# pads.net
KiCad netlist of a schematic drawn in EAGLE
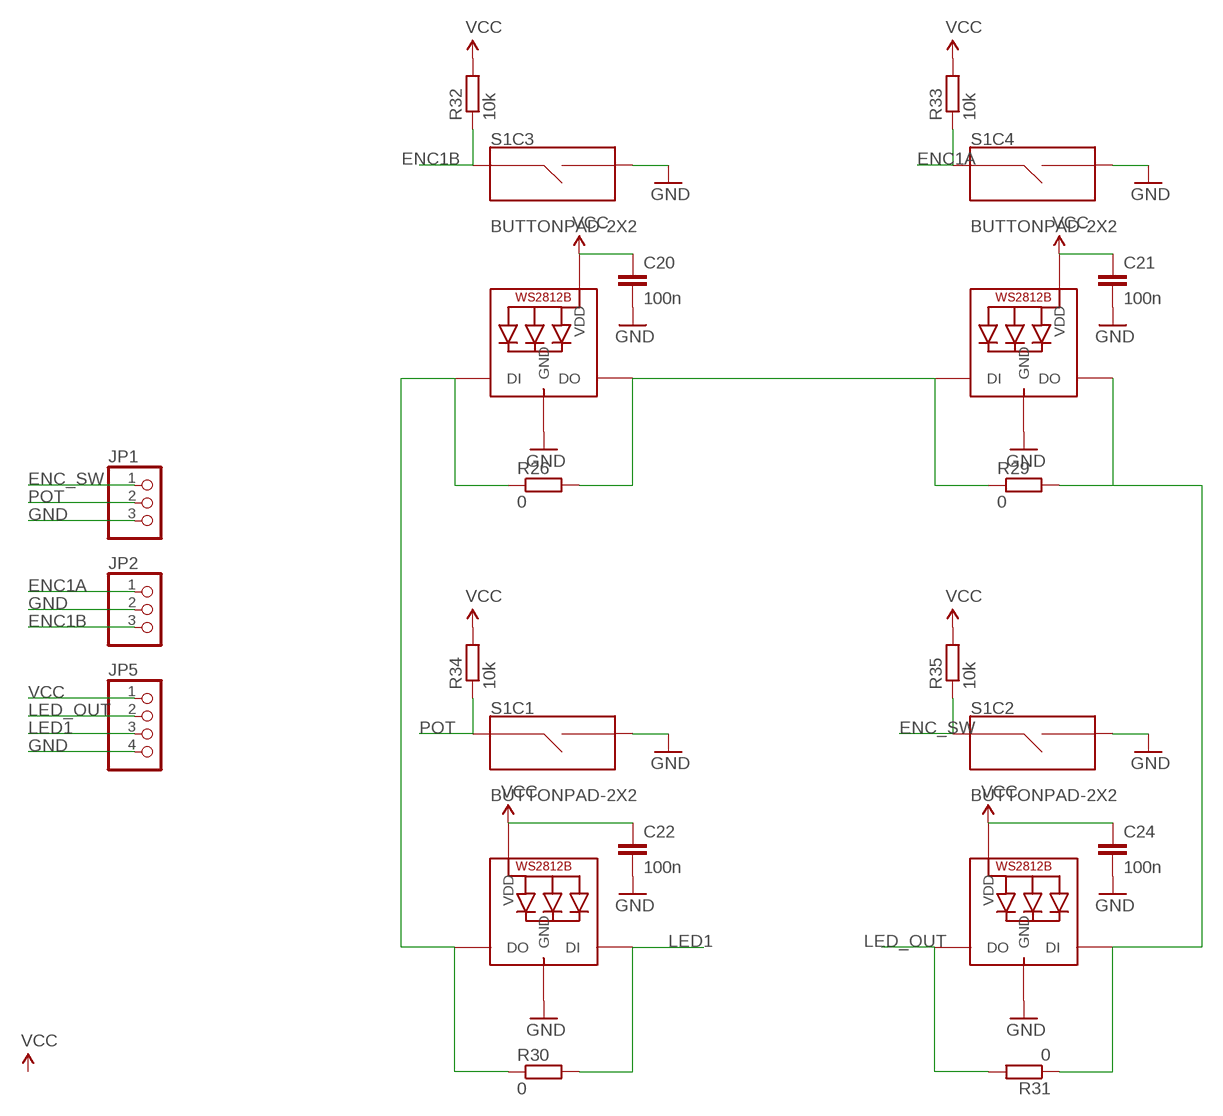
[diagram p0: schematic, sheet 1]

(export (version "E")
  (design (tool "Eeschema 10.0.6"))
  (components
    (comp (ref "C20")
      (value "100n")
      (footprint "eagle-import:0603-CAP")
      (libsource (lib "eagle-import") (part "CAP0603-CAP"))
    )
    (comp (ref "C21")
      (value "100n")
      (footprint "eagle-import:0603-CAP")
      (libsource (lib "eagle-import") (part "CAP0603-CAP"))
    )
    (comp (ref "C22")
      (value "100n")
      (footprint "eagle-import:0603-CAP")
      (libsource (lib "eagle-import") (part "CAP0603-CAP"))
    )
    (comp (ref "C24")
      (value "100n")
      (footprint "eagle-import:0603-CAP")
      (libsource (lib "eagle-import") (part "CAP0603-CAP"))
    )
    (comp (ref "JP1")
      (value "PINHD-1X31X03_SMT")
      (footprint "eagle-import:1X03_SMT")
      (libsource (lib "eagle-import") (part "PINHD-1X31X03_SMT"))
    )
    (comp (ref "JP2")
      (value "PINHD-1X31X03_SMT")
      (footprint "eagle-import:1X03_SMT")
      (libsource (lib "eagle-import") (part "PINHD-1X31X03_SMT"))
    )
    (comp (ref "JP5")
      (value "PINHD-1X41X04_SMT")
      (footprint "eagle-import:1X04_SMT")
      (libsource (lib "eagle-import") (part "PINHD-1X41X04_SMT"))
    )
    (comp (ref "LED16")
      (value "WS2812B3535")
      (footprint "eagle-import:LED3535")
      (libsource (lib "eagle-import") (part "WS2812B3535"))
    )
    (comp (ref "LED17")
      (value "WS2812B3535")
      (footprint "eagle-import:LED3535")
      (libsource (lib "eagle-import") (part "WS2812B3535"))
    )
    (comp (ref "LED18")
      (value "WS2812B3535")
      (footprint "eagle-import:LED3535")
      (libsource (lib "eagle-import") (part "WS2812B3535"))
    )
    (comp (ref "LED19")
      (value "WS2812B3535")
      (footprint "eagle-import:LED3535")
      (libsource (lib "eagle-import") (part "WS2812B3535"))
    )
    (comp (ref "R26")
      (value "0")
      (footprint "eagle-import:R0603")
      (libsource (lib "eagle-import") (part "R-EU_R0603"))
    )
    (comp (ref "R29")
      (value "0")
      (footprint "eagle-import:R0603")
      (libsource (lib "eagle-import") (part "R-EU_R0603"))
    )
    (comp (ref "R30")
      (value "0")
      (footprint "eagle-import:R0603")
      (libsource (lib "eagle-import") (part "R-EU_R0603"))
    )
    (comp (ref "R31")
      (value "0")
      (footprint "eagle-import:R0603")
      (libsource (lib "eagle-import") (part "R-EU_R0603"))
    )
    (comp (ref "R32")
      (value "10k")
      (footprint "eagle-import:R0603")
      (libsource (lib "eagle-import") (part "R-EU_R0603"))
    )
    (comp (ref "R33")
      (value "10k")
      (footprint "eagle-import:R0603")
      (libsource (lib "eagle-import") (part "R-EU_R0603"))
    )
    (comp (ref "R34")
      (value "10k")
      (footprint "eagle-import:R0603")
      (libsource (lib "eagle-import") (part "R-EU_R0603"))
    )
    (comp (ref "R35")
      (value "10k")
      (footprint "eagle-import:R0603")
      (libsource (lib "eagle-import") (part "R-EU_R0603"))
    )
    (comp (ref "S1")
      (value "BUTTONPAD-2X2")
      (footprint "eagle-import:BUTTONPAD-2X2-SINGLE")
      (libsource (lib "eagle-import") (part "BUTTONPAD-2X2"))
    )
  )
  (nets
    (net (code "1") (name "/ENC1A") (class "Default")
      (node (ref "JP2") (pin "1") (pinfunction "1_1") (pintype "passive"))
      (node (ref "R33") (pin "1") (pinfunction "1_1") (pintype "passive"))
      (node (ref "S1") (pin "SIG7") (pinfunction "SIG1_SIG7") (pintype "bidirectional"))
    )
    (net (code "2") (name "/ENC1B") (class "Default")
      (node (ref "JP2") (pin "3") (pinfunction "3_3") (pintype "passive"))
      (node (ref "R32") (pin "1") (pinfunction "1_1") (pintype "passive"))
      (node (ref "S1") (pin "SIG5") (pinfunction "SIG1_SIG5") (pintype "bidirectional"))
    )
    (net (code "3") (name "/ENC_SW") (class "Default")
      (node (ref "JP1") (pin "1") (pinfunction "1_1") (pintype "passive"))
      (node (ref "R35") (pin "1") (pinfunction "1_1") (pintype "passive"))
      (node (ref "S1") (pin "SIG3") (pinfunction "SIG1_SIG3") (pintype "bidirectional"))
    )
    (net (code "4") (name "/LED1") (class "Default")
      (node (ref "JP5") (pin "3") (pinfunction "3_3") (pintype "passive"))
      (node (ref "LED16") (pin "1") (pinfunction "DI_1") (pintype "input"))
      (node (ref "R30") (pin "2") (pinfunction "2_2") (pintype "passive"))
    )
    (net (code "5") (name "/LED_OUT") (class "Default")
      (node (ref "JP5") (pin "2") (pinfunction "2_2") (pintype "passive"))
      (node (ref "LED17") (pin "3") (pinfunction "DO_3") (pintype "output"))
      (node (ref "R31") (pin "2") (pinfunction "2_2") (pintype "passive"))
    )
    (net (code "6") (name "/POT") (class "Default")
      (node (ref "JP1") (pin "2") (pinfunction "2_2") (pintype "passive"))
      (node (ref "R34") (pin "1") (pinfunction "1_1") (pintype "passive"))
      (node (ref "S1") (pin "SIG1") (pinfunction "SIG1_SIG1") (pintype "bidirectional"))
    )
    (net (code "7") (name "GND") (class "Default")
      (node (ref "C20") (pin "2") (pinfunction "2_2") (pintype "passive"))
      (node (ref "C21") (pin "2") (pinfunction "2_2") (pintype "passive"))
      (node (ref "C22") (pin "2") (pinfunction "2_2") (pintype "passive"))
      (node (ref "C24") (pin "2") (pinfunction "2_2") (pintype "passive"))
      (node (ref "JP1") (pin "3") (pinfunction "3_3") (pintype "passive"))
      (node (ref "JP2") (pin "2") (pinfunction "2_2") (pintype "passive"))
      (node (ref "JP5") (pin "4") (pinfunction "4_4") (pintype "passive"))
      (node (ref "LED16") (pin "4") (pinfunction "GND_4") (pintype "power_in"))
      (node (ref "LED17") (pin "4") (pinfunction "GND_4") (pintype "power_in"))
      (node (ref "LED18") (pin "4") (pinfunction "GND_4") (pintype "power_in"))
      (node (ref "LED19") (pin "4") (pinfunction "GND_4") (pintype "power_in"))
      (node (ref "S1") (pin "SIG2") (pinfunction "SIG2_SIG2") (pintype "bidirectional"))
      (node (ref "S1") (pin "SIG4") (pinfunction "SIG2_SIG4") (pintype "bidirectional"))
      (node (ref "S1") (pin "SIG6") (pinfunction "SIG2_SIG6") (pintype "bidirectional"))
      (node (ref "S1") (pin "SIG8") (pinfunction "SIG2_SIG8") (pintype "bidirectional"))
    )
    (net (code "8") (name "Net-(LED16-DO)") (class "Default")
      (node (ref "LED16") (pin "3") (pinfunction "DO_3") (pintype "output"))
      (node (ref "LED18") (pin "1") (pinfunction "DI_1") (pintype "input"))
      (node (ref "R26") (pin "1") (pinfunction "1_1") (pintype "passive"))
      (node (ref "R30") (pin "1") (pinfunction "1_1") (pintype "passive"))
    )
    (net (code "9") (name "Net-(LED17-DI)") (class "Default")
      (node (ref "LED17") (pin "1") (pinfunction "DI_1") (pintype "input"))
      (node (ref "LED19") (pin "3") (pinfunction "DO_3") (pintype "output"))
      (node (ref "R29") (pin "2") (pinfunction "2_2") (pintype "passive"))
      (node (ref "R31") (pin "1") (pinfunction "1_1") (pintype "passive"))
    )
    (net (code "10") (name "Net-(LED18-DO)") (class "Default")
      (node (ref "LED18") (pin "3") (pinfunction "DO_3") (pintype "output"))
      (node (ref "LED19") (pin "1") (pinfunction "DI_1") (pintype "input"))
      (node (ref "R26") (pin "2") (pinfunction "2_2") (pintype "passive"))
      (node (ref "R29") (pin "1") (pinfunction "1_1") (pintype "passive"))
    )
    (net (code "11") (name "VCC") (class "Default")
      (node (ref "C20") (pin "1") (pinfunction "1_1") (pintype "passive"))
      (node (ref "C21") (pin "1") (pinfunction "1_1") (pintype "passive"))
      (node (ref "C22") (pin "1") (pinfunction "1_1") (pintype "passive"))
      (node (ref "C24") (pin "1") (pinfunction "1_1") (pintype "passive"))
      (node (ref "JP5") (pin "1") (pinfunction "1_1") (pintype "passive"))
      (node (ref "LED16") (pin "2") (pinfunction "VDD_2") (pintype "power_in"))
      (node (ref "LED17") (pin "2") (pinfunction "VDD_2") (pintype "power_in"))
      (node (ref "LED18") (pin "2") (pinfunction "VDD_2") (pintype "power_in"))
      (node (ref "LED19") (pin "2") (pinfunction "VDD_2") (pintype "power_in"))
      (node (ref "R32") (pin "2") (pinfunction "2_2") (pintype "passive"))
      (node (ref "R33") (pin "2") (pinfunction "2_2") (pintype "passive"))
      (node (ref "R34") (pin "2") (pinfunction "2_2") (pintype "passive"))
      (node (ref "R35") (pin "2") (pinfunction "2_2") (pintype "passive"))
    )
  )
)
